# AMS1117-3_3V.net
KiCad netlist of a schematic drawn in Altium Designer
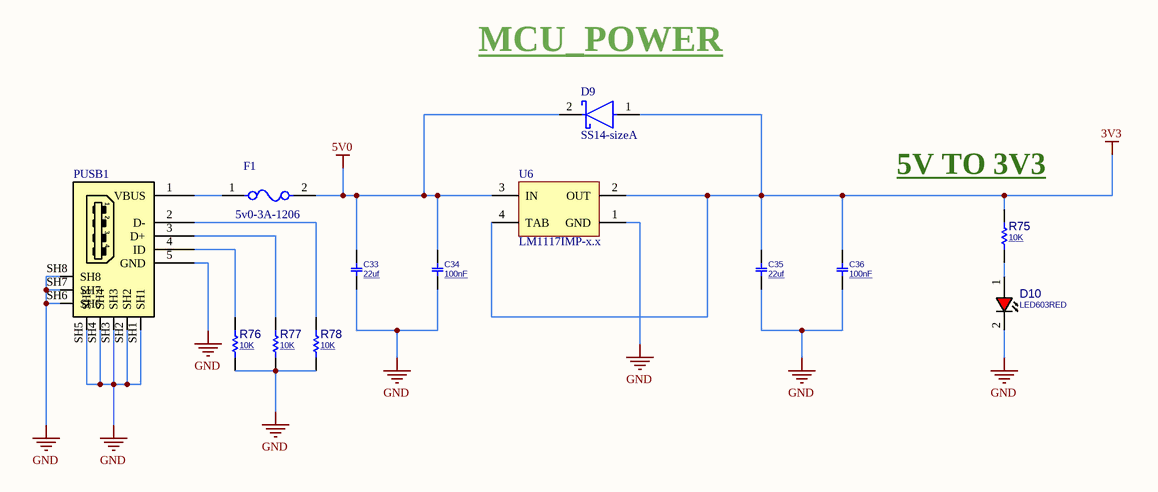
[diagram p0: AMS1117-3.3V.SchDoc]

(export (version "E")
  (design (tool "Eeschema 10.0.6"))
  (components
    (comp (ref "C33")
      (value "22uf")
      (footprint "C1206")
      (description "CAP, MLCC, -F, -V, MATERIAL, -%, 0201")
      (fields (field (name "MANF_P#") "MANF_PART#"))
      (libsource (lib "passive_smd") (part "CAP_SMD_MLCC_1206"))
    )
    (comp (ref "C34")
      (value "100nF")
      (footprint "C0603")
      (description "CAP, MLCC, -F, -V, MATERIAL, -%, 0201")
      (fields (field (name "MANF_P#") "MANF_PART#"))
      (libsource (lib "passive_smd") (part "CAP_SMD_MLCC_0603"))
    )
    (comp (ref "C35")
      (value "22uf")
      (footprint "C1206")
      (description "CAP, MLCC, -F, -V, MATERIAL, -%, 0201")
      (fields (field (name "MANF_P#") "MANF_PART#"))
      (libsource (lib "passive_smd") (part "CAP_SMD_MLCC_1206"))
    )
    (comp (ref "C36")
      (value "100nF")
      (footprint "C0603")
      (description "CAP, MLCC, -F, -V, MATERIAL, -%, 0201")
      (fields (field (name "MANF_P#") "MANF_PART#"))
      (libsource (lib "passive_smd") (part "CAP_SMD_MLCC_0603"))
    )
    (comp (ref "D9")
      (value "SS14-sizeA")
      (footprint "FP-403AE-MFG")
      (description "DIODE SCHOTTKY 40V 1A SMA")
      (fields
        (field (name "MANUFACTURER PART NUMBER") "SS14")
        (field (name "MANUFACTURER") "ON Semiconductor")
      )
      (libsource (lib "ss14-sizeA") (part "ss14"))
    )
    (comp (ref "D10")
      (value "LED603RED")
      (footprint "LED0603RED")
      (description "LED, SMD, 0603, RED")
      (fields (field (name "MANF") "MANF") (field (name "MANF_P#") "MANF_PART#"))
      (libsource (lib "led(diode)") (part "LED_SMD_0603_RED"))
    )
    (comp (ref "F1")
      (value "5v0-3A-1206")
      (footprint "FP-nanoSMDC-MFG")
      (description "PTC RESET FUSE 48V 120MA 1206")
      (fields
        (field (name "MANUFACTURER") "Littelfuse")
        (field (name "MANUFACTURER PART NUMBER") "NANOSMDC012F-2")
      )
      (libsource (lib "Altium Content Vault") (part "5bcf9b9f640e542cf0359d10258e979"))
    )
    (comp (ref "PUSB1")
      (value "CONN_USB_MICROB")
      (footprint "USB_MICRO_B_BM_SHS")
      (description "CONN, USB, MICRO B, R/A, SMD, BOTTOM MOUNT")
      (fields (field (name "MANF_P#") "47346-0001") (field (name "MANF") "Molex"))
      (libsource (lib "conn_usb") (part "CONN_USB_MICRO_B_BM_SHS"))
    )
    (comp (ref "R75")
      (value "10K")
      (footprint "R0603")
      (description "RESISTOR, SMD")
      (libsource (lib "passive_smd") (part "RES_SMD"))
    )
    (comp (ref "R76")
      (value "10K")
      (footprint "R0603")
      (description "RESISTOR, SMD")
      (libsource (lib "passive_smd") (part "RES_SMD"))
    )
    (comp (ref "R77")
      (value "10K")
      (footprint "R0603")
      (description "RESISTOR, SMD")
      (libsource (lib "passive_smd") (part "RES_SMD"))
    )
    (comp (ref "R78")
      (value "10K")
      (footprint "R0603")
      (description "RESISTOR, SMD")
      (libsource (lib "passive_smd") (part "RES_SMD"))
    )
    (comp (ref "U6")
      (value "LM1117IMP-x.x")
      (footprint "SOT223")
      (description "x.x Volt, 800mA Low-Dropout Linear Regulator, 4-pin SOT-223")
      (libsource (lib "Regulator") (part "LM1117IMP-x.x"))
    )
  )
  (nets
    (net (code "1") (name "3V3") (class "Default")
      (node (ref "C35") (pin "2") (pinfunction "2_2") (pintype "passive"))
      (node (ref "C36") (pin "2") (pinfunction "2_2") (pintype "passive"))
      (node (ref "D9") (pin "1") (pinfunction "A_1") (pintype "passive"))
      (node (ref "R75") (pin "1") (pinfunction "1_1") (pintype "passive"))
      (node (ref "U6") (pin "2") (pinfunction "OUT_2") (pintype "power_in"))
      (node (ref "U6") (pin "4") (pinfunction "TAB_4") (pintype "power_in"))
    )
    (net (code "2") (name "5V0") (class "Default")
      (node (ref "C33") (pin "2") (pinfunction "2_2") (pintype "passive"))
      (node (ref "C34") (pin "2") (pinfunction "2_2") (pintype "passive"))
      (node (ref "D9") (pin "2") (pinfunction "C_2") (pintype "passive"))
      (node (ref "F1") (pin "2") (pinfunction "2_2") (pintype "passive"))
      (node (ref "U6") (pin "3") (pinfunction "IN_3") (pintype "power_in"))
    )
    (net (code "3") (name "GND") (class "Default")
      (node (ref "C33") (pin "1") (pinfunction "1_1") (pintype "passive"))
      (node (ref "C34") (pin "1") (pinfunction "1_1") (pintype "passive"))
      (node (ref "C35") (pin "1") (pinfunction "1_1") (pintype "passive"))
      (node (ref "C36") (pin "1") (pinfunction "1_1") (pintype "passive"))
      (node (ref "D10") (pin "2") (pinfunction "CATHODE_2") (pintype "passive"))
      (node (ref "PUSB1") (pin "5") (pinfunction "GND_5") (pintype "power_in"))
      (node (ref "PUSB1") (pin "SH1") (pinfunction "SH1_SH1") (pintype "passive"))
      (node (ref "PUSB1") (pin "SH2") (pinfunction "SH2_SH2") (pintype "passive"))
      (node (ref "PUSB1") (pin "SH3") (pinfunction "SH3_SH3") (pintype "passive"))
      (node (ref "PUSB1") (pin "SH4") (pinfunction "SH4_SH4") (pintype "passive"))
      (node (ref "PUSB1") (pin "SH5") (pinfunction "SH5_SH5") (pintype "passive"))
      (node (ref "PUSB1") (pin "SH6") (pinfunction "SH6_SH6") (pintype "passive"))
      (node (ref "PUSB1") (pin "SH7") (pinfunction "SH7_SH7") (pintype "passive"))
      (node (ref "PUSB1") (pin "SH8") (pinfunction "SH8_SH8") (pintype "passive"))
      (node (ref "R76") (pin "2") (pinfunction "2_2") (pintype "passive"))
      (node (ref "R77") (pin "2") (pinfunction "2_2") (pintype "passive"))
      (node (ref "R78") (pin "2") (pinfunction "2_2") (pintype "passive"))
      (node (ref "U6") (pin "1") (pinfunction "GND_1") (pintype "power_in"))
    )
    (net (code "4") (name "Net-(D10-ANODE)") (class "Default")
      (node (ref "D10") (pin "1") (pinfunction "ANODE_1") (pintype "passive"))
      (node (ref "R75") (pin "2") (pinfunction "2_2") (pintype "passive"))
    )
    (net (code "5") (name "Net-(PUSB1-D+)") (class "Default")
      (node (ref "PUSB1") (pin "3") (pinfunction "D+_3") (pintype "passive"))
      (node (ref "R77") (pin "1") (pinfunction "1_1") (pintype "passive"))
    )
    (net (code "6") (name "Net-(PUSB1-D-)") (class "Default")
      (node (ref "PUSB1") (pin "2") (pinfunction "D-_2") (pintype "passive"))
      (node (ref "R78") (pin "1") (pinfunction "1_1") (pintype "passive"))
    )
    (net (code "7") (name "Net-(PUSB1-ID)") (class "Default")
      (node (ref "PUSB1") (pin "4") (pinfunction "ID_4") (pintype "power_in"))
      (node (ref "R76") (pin "1") (pinfunction "1_1") (pintype "passive"))
    )
    (net (code "8") (name "Net-(PUSB1-VBUS)") (class "Default")
      (node (ref "F1") (pin "1") (pinfunction "1_1") (pintype "passive"))
      (node (ref "PUSB1") (pin "1") (pinfunction "VBUS_1") (pintype "power_in"))
    )
  )
)
